# McParticleEthernetFace-V1.net
KiCad netlist of a schematic drawn in EAGLE
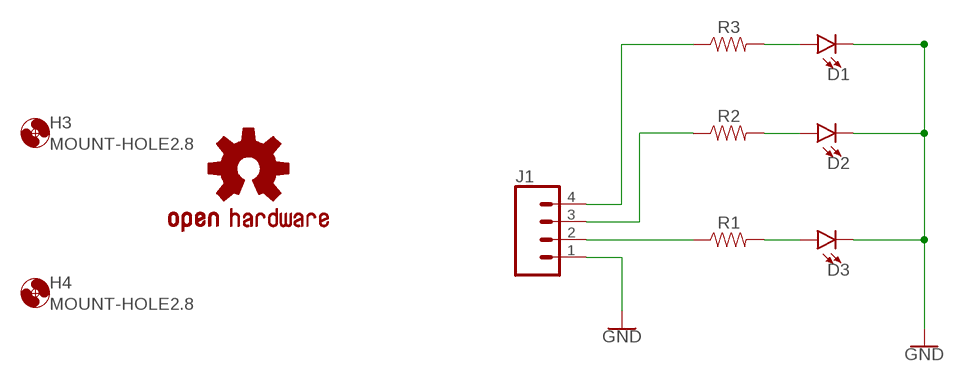
[diagram p0: schematic, sheet 1]

(export (version "E")
  (design (tool "Eeschema 10.0.6"))
  (components
    (comp (ref "D1")
      (value "LED1206-BOTTOM-1.6MM")
      (footprint "eagle-import:LED-1206-BOTTOM-1.6MM")
      (libsource (lib "eagle-import") (part "LED1206-BOTTOM-1.6MM"))
    )
    (comp (ref "D2")
      (value "LED1206-BOTTOM-1.6MM")
      (footprint "eagle-import:LED-1206-BOTTOM-1.6MM")
      (libsource (lib "eagle-import") (part "LED1206-BOTTOM-1.6MM"))
    )
    (comp (ref "D3")
      (value "LED1206-BOTTOM-1.6MM")
      (footprint "eagle-import:LED-1206-BOTTOM-1.6MM")
      (libsource (lib "eagle-import") (part "LED1206-BOTTOM-1.6MM"))
    )
    (comp (ref "H3")
      (value "MOUNT-HOLE2.8")
      (footprint "eagle-import:2,8")
      (libsource (lib "eagle-import") (part "MOUNT-HOLE2.8"))
    )
    (comp (ref "H4")
      (value "MOUNT-HOLE2.8")
      (footprint "eagle-import:2,8")
      (libsource (lib "eagle-import") (part "MOUNT-HOLE2.8"))
    )
    (comp (ref "J1")
      (value "CONN_04SMD2")
      (footprint "eagle-import:1X04_1MM_RA")
      (libsource (lib "eagle-import") (part "CONN_04SMD2"))
    )
    (comp (ref "LOGO1")
      (value "OSHW-LOGOL")
      (footprint "eagle-import:OSHW-LOGO-L")
      (libsource (lib "eagle-import") (part "OSHW-LOGOL"))
    )
    (comp (ref "R1")
      (value "RESISTOR0805")
      (footprint "eagle-import:0805")
      (libsource (lib "eagle-import") (part "RESISTOR0805"))
    )
    (comp (ref "R2")
      (value "RESISTOR0805")
      (footprint "eagle-import:0805")
      (libsource (lib "eagle-import") (part "RESISTOR0805"))
    )
    (comp (ref "R3")
      (value "RESISTOR0805")
      (footprint "eagle-import:0805")
      (libsource (lib "eagle-import") (part "RESISTOR0805"))
    )
  )
  (nets
    (net (code "1") (name "GND") (class "Default")
      (node (ref "D1") (pin "C") (pinfunction "C_C") (pintype "passive"))
      (node (ref "D2") (pin "C") (pinfunction "C_C") (pintype "passive"))
      (node (ref "D3") (pin "C") (pinfunction "C_C") (pintype "passive"))
      (node (ref "J1") (pin "1") (pinfunction "1_1") (pintype "passive"))
    )
    (net (code "2") (name "Net-(D1-PadA)") (class "Default")
      (node (ref "D1") (pin "A") (pinfunction "A_A") (pintype "passive"))
      (node (ref "R3") (pin "2") (pinfunction "2_2") (pintype "passive"))
    )
    (net (code "3") (name "Net-(D2-PadA)") (class "Default")
      (node (ref "D2") (pin "A") (pinfunction "A_A") (pintype "passive"))
      (node (ref "R2") (pin "2") (pinfunction "2_2") (pintype "passive"))
    )
    (net (code "4") (name "Net-(D3-PadA)") (class "Default")
      (node (ref "D3") (pin "A") (pinfunction "A_A") (pintype "passive"))
      (node (ref "R1") (pin "2") (pinfunction "2_2") (pintype "passive"))
    )
    (net (code "5") (name "Net-(J1-Pad2)") (class "Default")
      (node (ref "J1") (pin "2") (pinfunction "2_2") (pintype "passive"))
      (node (ref "R1") (pin "1") (pinfunction "1_1") (pintype "passive"))
    )
    (net (code "6") (name "Net-(J1-Pad3)") (class "Default")
      (node (ref "J1") (pin "3") (pinfunction "3_3") (pintype "passive"))
      (node (ref "R2") (pin "1") (pinfunction "1_1") (pintype "passive"))
    )
    (net (code "7") (name "Net-(J1-Pad4)") (class "Default")
      (node (ref "J1") (pin "4") (pinfunction "4_4") (pintype "passive"))
      (node (ref "R3") (pin "1") (pinfunction "1_1") (pintype "passive"))
    )
  )
)
